# MCU_Module_V2.net
KiCad netlist of a schematic drawn in EAGLE
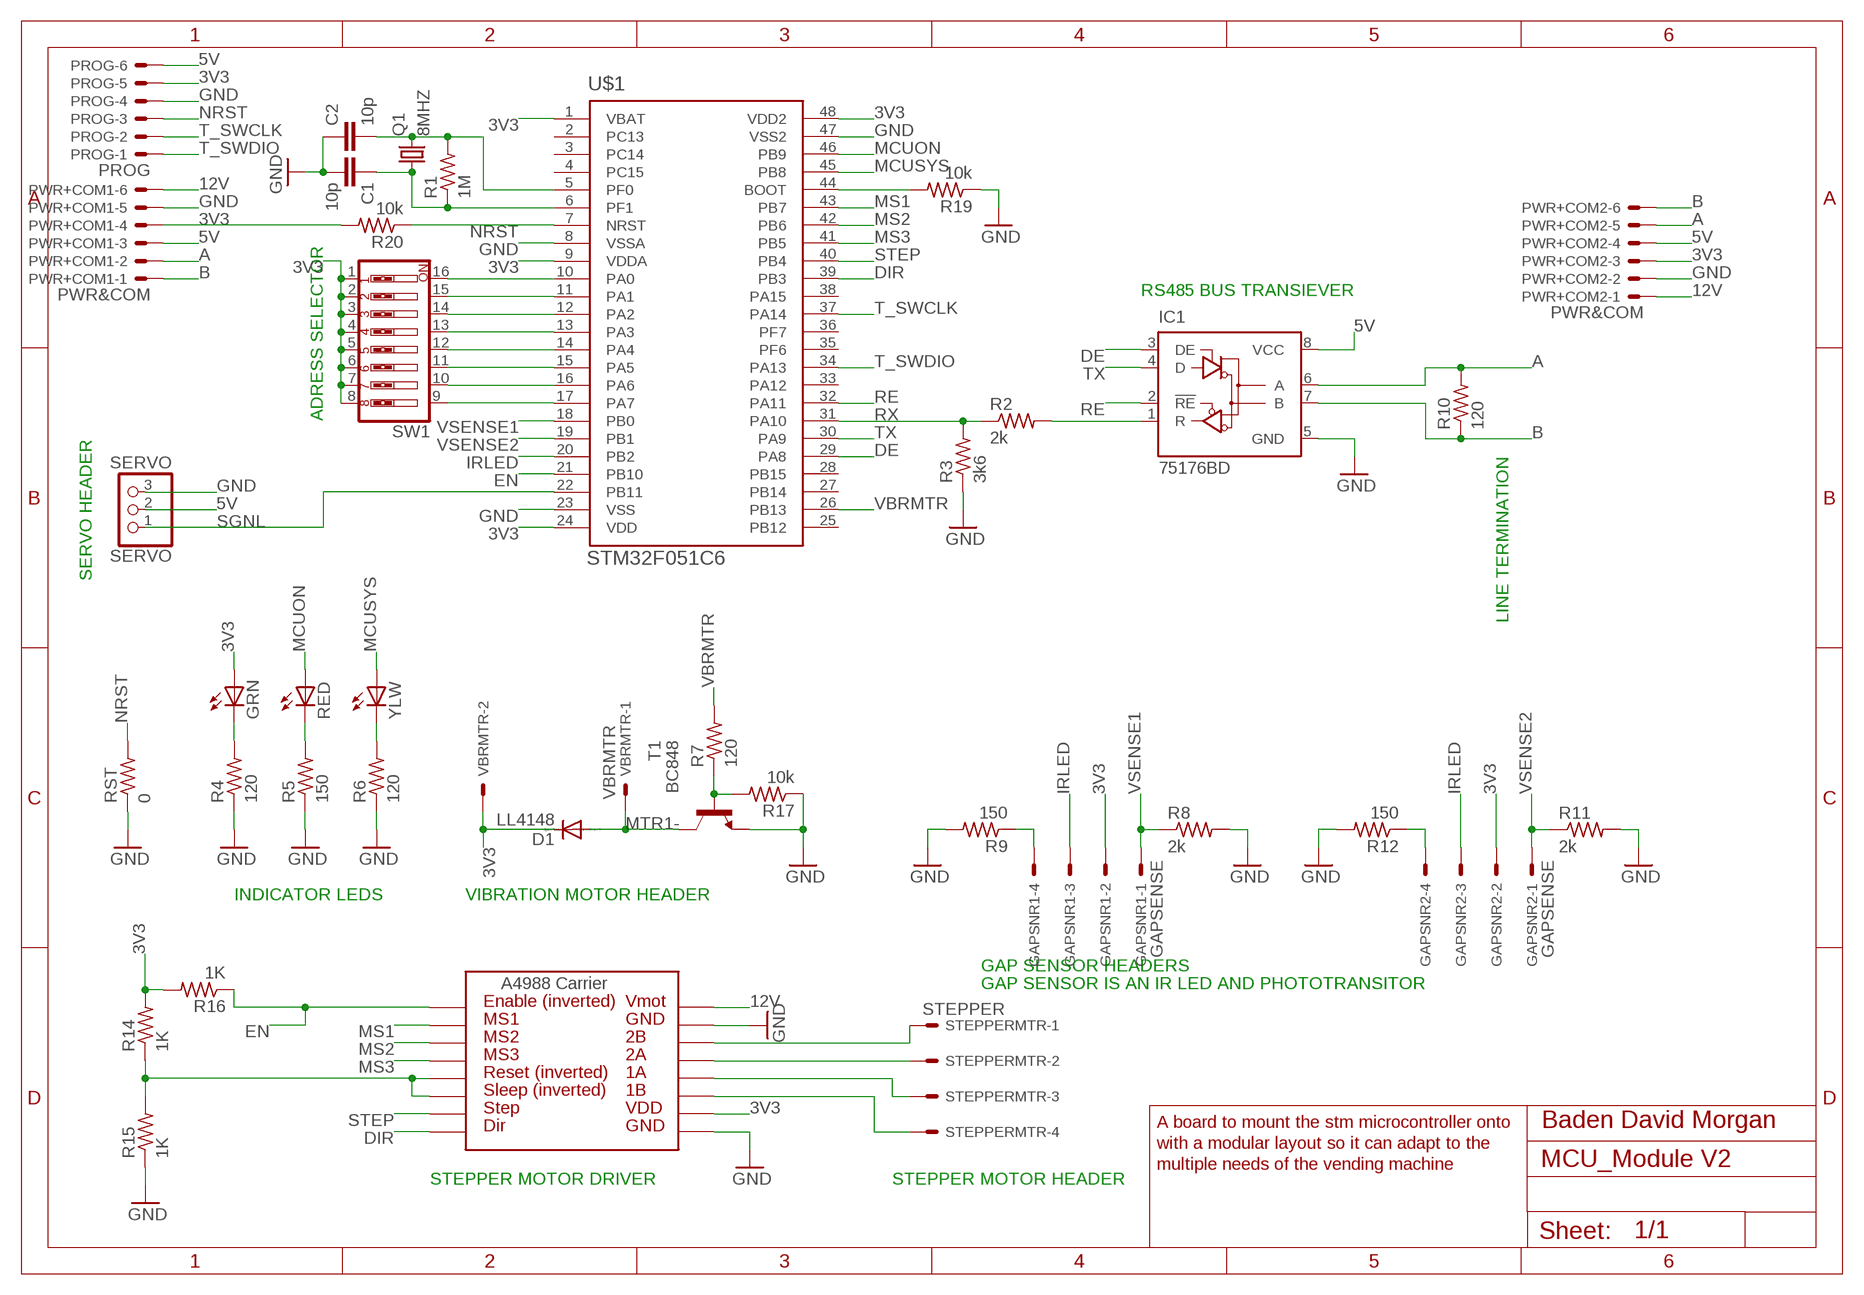
[diagram p0: schematic, sheet 1]

(export (version "E")
  (design (tool "Eeschema 10.0.6"))
  (components
    (comp (ref "C1")
      (value "10p")
      (footprint "eagle-import:C0805")
      (libsource (lib "eagle-import") (part "C-EUC0805"))
    )
    (comp (ref "C2")
      (value "10p")
      (footprint "eagle-import:C0805")
      (libsource (lib "eagle-import") (part "C-EUC0805"))
    )
    (comp (ref "D1")
      (value "LL4148")
      (footprint "eagle-import:SOD80C")
      (libsource (lib "eagle-import") (part "PMLL4150"))
    )
    (comp (ref "GAPSNR1")
      (value "GAPSENSE")
      (footprint "eagle-import:6410-04")
      (libsource (lib "eagle-import") (part "22-?-0427-2041"))
    )
    (comp (ref "GAPSNR2")
      (value "GAPSENSE")
      (footprint "eagle-import:6410-04")
      (libsource (lib "eagle-import") (part "22-?-0427-2041"))
    )
    (comp (ref "GRN")
      (value "LEDSML1206")
      (footprint "eagle-import:SML1206")
      (libsource (lib "eagle-import") (part "LEDSML1206"))
    )
    (comp (ref "IC1")
      (value "75176BD")
      (footprint "eagle-import:D_R-PDSO-G8")
      (libsource (lib "eagle-import") (part "75176AD"))
    )
    (comp (ref "PROG")
      (value "PROG")
      (footprint "eagle-import:6410-06")
      (libsource (lib "eagle-import") (part "22-?-0627-2061"))
    )
    (comp (ref "PWR+COM1")
      (value "PWR&COM")
      (footprint "eagle-import:7395-06")
      (libsource (lib "eagle-import") (part "22-?-0605-7068"))
    )
    (comp (ref "PWR+COM2")
      (value "PWR&COM")
      (footprint "eagle-import:7395-06")
      (libsource (lib "eagle-import") (part "22-?-0605-7068"))
    )
    (comp (ref "Q1")
      (value "8MHZ")
      (footprint "eagle-import:SM49")
      (libsource (lib "eagle-import") (part "CRYSTALSM49"))
    )
    (comp (ref "R1")
      (value "1M")
      (footprint "eagle-import:R0805")
      (libsource (lib "eagle-import") (part "R-US_R0805"))
    )
    (comp (ref "R2")
      (value "2k")
      (footprint "eagle-import:R0805")
      (libsource (lib "eagle-import") (part "resistor_R-US_R0805"))
    )
    (comp (ref "R3")
      (value "3k6")
      (footprint "eagle-import:R0805")
      (libsource (lib "eagle-import") (part "resistor_R-US_R0805"))
    )
    (comp (ref "R4")
      (value "120")
      (footprint "eagle-import:R0805")
      (libsource (lib "eagle-import") (part "R-US_R0805"))
    )
    (comp (ref "R5")
      (value "150")
      (footprint "eagle-import:R0805")
      (libsource (lib "eagle-import") (part "R-US_R0805"))
    )
    (comp (ref "R6")
      (value "120")
      (footprint "eagle-import:R0805")
      (libsource (lib "eagle-import") (part "R-US_R0805"))
    )
    (comp (ref "R7")
      (value "120")
      (footprint "eagle-import:R0805")
      (libsource (lib "eagle-import") (part "R-US_R0805"))
    )
    (comp (ref "R8")
      (value "2k")
      (footprint "eagle-import:R0805")
      (libsource (lib "eagle-import") (part "resistor_R-US_R0805"))
    )
    (comp (ref "R9")
      (value "150")
      (footprint "eagle-import:R0805")
      (libsource (lib "eagle-import") (part "R-US_R0805"))
    )
    (comp (ref "R10")
      (value "120")
      (footprint "eagle-import:R0805")
      (libsource (lib "eagle-import") (part "resistor_R-US_R0805"))
    )
    (comp (ref "R11")
      (value "2k")
      (footprint "eagle-import:R0805")
      (libsource (lib "eagle-import") (part "resistor_R-US_R0805"))
    )
    (comp (ref "R12")
      (value "150")
      (footprint "eagle-import:R0805")
      (libsource (lib "eagle-import") (part "R-US_R0805"))
    )
    (comp (ref "R14")
      (value "1K")
      (footprint "eagle-import:R0805")
      (libsource (lib "eagle-import") (part "R-US_R0805"))
    )
    (comp (ref "R15")
      (value "1K")
      (footprint "eagle-import:R0805")
      (libsource (lib "eagle-import") (part "R-US_R0805"))
    )
    (comp (ref "R16")
      (value "1K")
      (footprint "eagle-import:R0805")
      (libsource (lib "eagle-import") (part "R-US_R0805"))
    )
    (comp (ref "R17")
      (value "10k")
      (footprint "eagle-import:R0805")
      (libsource (lib "eagle-import") (part "R-US_R0805"))
    )
    (comp (ref "R19")
      (value "10k")
      (footprint "eagle-import:R0805")
      (libsource (lib "eagle-import") (part "R-US_R0805"))
    )
    (comp (ref "R20")
      (value "10k")
      (footprint "eagle-import:R0805")
      (libsource (lib "eagle-import") (part "R-US_R0805"))
    )
    (comp (ref "RED")
      (value "LEDSML1206")
      (footprint "eagle-import:SML1206")
      (libsource (lib "eagle-import") (part "LEDSML1206"))
    )
    (comp (ref "RST")
      (value "0")
      (footprint "eagle-import:R0805")
      (libsource (lib "eagle-import") (part "R-US_R0805"))
    )
    (comp (ref "SERVO")
      (value "SERVO")
      (footprint "eagle-import:1X03")
      (libsource (lib "eagle-import") (part "PINHD-1X3"))
    )
    (comp (ref "STEPPERMTR")
      (value "STEPPER")
      (footprint "eagle-import:6410-04")
      (libsource (lib "eagle-import") (part "22-?-0427-2041"))
    )
    (comp (ref "SW1")
      (value "SW_DIP-8")
      (footprint "eagle-import:EDG-08")
      (libsource (lib "eagle-import") (part "SW_DIP-8"))
    )
    (comp (ref "T1")
      (value "BC848")
      (footprint "eagle-import:SOT23")
      (libsource (lib "eagle-import") (part "BC848"))
    )
    (comp (ref "U$1")
      (value "STM32F051C6")
      (footprint "eagle-import:QFP50P900X900X160-48N")
      (libsource (lib "eagle-import") (part "STM32F051C6"))
    )
    (comp (ref "U$2")
      (value "A4983CARRIER")
      (footprint "eagle-import:A4988BREAKOUT")
      (libsource (lib "eagle-import") (part "A4983CARRIER"))
    )
    (comp (ref "VBRMTR")
      (value "VBRMTR")
      (footprint "eagle-import:6410-02")
      (libsource (lib "eagle-import") (part "22-?-0227-2021"))
    )
    (comp (ref "YLW")
      (value "LEDSML1206")
      (footprint "eagle-import:SML1206")
      (libsource (lib "eagle-import") (part "LEDSML1206"))
    )
  )
  (nets
    (net (code "1") (name "/3V3") (class "Default")
      (node (ref "D1") (pin "C") (pinfunction "C_C") (pintype "passive"))
      (node (ref "GAPSNR1") (pin "2") (pinfunction "S_2") (pintype "passive"))
      (node (ref "GAPSNR2") (pin "2") (pinfunction "S_2") (pintype "passive"))
      (node (ref "GRN") (pin "A") (pinfunction "A_A") (pintype "passive"))
      (node (ref "PROG") (pin "5") (pinfunction "S_5") (pintype "passive"))
      (node (ref "PWR+COM1") (pin "4") (pinfunction "S_4") (pintype "passive"))
      (node (ref "PWR+COM2") (pin "3") (pinfunction "S_3") (pintype "passive"))
      (node (ref "R14") (pin "2") (pinfunction "2_2") (pintype "passive"))
      (node (ref "R16") (pin "2") (pinfunction "2_2") (pintype "passive"))
      (node (ref "R20") (pin "2") (pinfunction "2_2") (pintype "passive"))
      (node (ref "SW1") (pin "1") (pinfunction "1_1") (pintype "passive"))
      (node (ref "SW1") (pin "2") (pinfunction "2_2") (pintype "passive"))
      (node (ref "SW1") (pin "3") (pinfunction "3_3") (pintype "passive"))
      (node (ref "SW1") (pin "4") (pinfunction "4_4") (pintype "passive"))
      (node (ref "SW1") (pin "5") (pinfunction "5_5") (pintype "passive"))
      (node (ref "SW1") (pin "6") (pinfunction "6_6") (pintype "passive"))
      (node (ref "SW1") (pin "7") (pinfunction "7_7") (pintype "passive"))
      (node (ref "SW1") (pin "8") (pinfunction "8_8") (pintype "passive"))
      (node (ref "U$1") (pin "1") (pinfunction "VBAT_1") (pintype "bidirectional"))
      (node (ref "U$1") (pin "24") (pinfunction "VDD_24") (pintype "bidirectional"))
      (node (ref "U$1") (pin "48") (pinfunction "VDD2_48") (pintype "bidirectional"))
      (node (ref "U$1") (pin "9") (pinfunction "VDDA_9") (pintype "bidirectional"))
      (node (ref "U$2") (pin "VDD") (pinfunction "VDD_VDD") (pintype "power_in"))
      (node (ref "VBRMTR") (pin "2") (pinfunction "S_2") (pintype "passive"))
    )
    (net (code "2") (name "/5V") (class "Default")
      (node (ref "IC1") (pin "8") (pinfunction "VCC_8") (pintype "power_in"))
      (node (ref "PROG") (pin "6") (pinfunction "S_6") (pintype "passive"))
      (node (ref "PWR+COM1") (pin "3") (pinfunction "S_3") (pintype "passive"))
      (node (ref "PWR+COM2") (pin "4") (pinfunction "S_4") (pintype "passive"))
      (node (ref "SERVO") (pin "2") (pinfunction "2_2") (pintype "passive"))
    )
    (net (code "3") (name "/12V") (class "Default")
      (node (ref "PWR+COM1") (pin "6") (pinfunction "S_6") (pintype "passive"))
      (node (ref "PWR+COM2") (pin "1") (pinfunction "S_1") (pintype "passive"))
      (node (ref "U$2") (pin "VMOT") (pinfunction "VMOT_VMOT") (pintype "power_in"))
    )
    (net (code "4") (name "/A") (class "Default")
      (node (ref "IC1") (pin "6") (pinfunction "A_6") (pintype "output"))
      (node (ref "PWR+COM1") (pin "2") (pinfunction "S_2") (pintype "passive"))
      (node (ref "PWR+COM2") (pin "5") (pinfunction "S_5") (pintype "passive"))
      (node (ref "R10") (pin "2") (pinfunction "2_2") (pintype "passive"))
    )
    (net (code "5") (name "/B") (class "Default")
      (node (ref "IC1") (pin "7") (pinfunction "B_7") (pintype "output"))
      (node (ref "PWR+COM1") (pin "1") (pinfunction "S_1") (pintype "passive"))
      (node (ref "PWR+COM2") (pin "6") (pinfunction "S_6") (pintype "passive"))
      (node (ref "R10") (pin "1") (pinfunction "1_1") (pintype "passive"))
    )
    (net (code "6") (name "/DE") (class "Default")
      (node (ref "IC1") (pin "3") (pinfunction "DE_3") (pintype "input"))
      (node (ref "U$1") (pin "29") (pinfunction "PA8_29") (pintype "bidirectional"))
    )
    (net (code "7") (name "/DIR") (class "Default")
      (node (ref "U$1") (pin "39") (pinfunction "PB3_39") (pintype "bidirectional"))
      (node (ref "U$2") (pin "DIR") (pinfunction "DIR_DIR") (pintype "input"))
    )
    (net (code "8") (name "/EN") (class "Default")
      (node (ref "R16") (pin "1") (pinfunction "1_1") (pintype "passive"))
      (node (ref "U$1") (pin "21") (pinfunction "PB10_21") (pintype "bidirectional"))
      (node (ref "U$2") (pin "EN") (pinfunction "EN_EN") (pintype "input"))
    )
    (net (code "9") (name "/IRLED") (class "Default")
      (node (ref "GAPSNR1") (pin "3") (pinfunction "S_3") (pintype "passive"))
      (node (ref "GAPSNR2") (pin "3") (pinfunction "S_3") (pintype "passive"))
      (node (ref "U$1") (pin "20") (pinfunction "PB2_20") (pintype "bidirectional"))
    )
    (net (code "10") (name "/MCUON") (class "Default")
      (node (ref "RED") (pin "A") (pinfunction "A_A") (pintype "passive"))
      (node (ref "U$1") (pin "46") (pinfunction "PB9_46") (pintype "bidirectional"))
    )
    (net (code "11") (name "/MCUSYS") (class "Default")
      (node (ref "U$1") (pin "45") (pinfunction "PB8_45") (pintype "bidirectional"))
      (node (ref "YLW") (pin "A") (pinfunction "A_A") (pintype "passive"))
    )
    (net (code "12") (name "/MS1") (class "Default")
      (node (ref "U$1") (pin "43") (pinfunction "PB7_43") (pintype "bidirectional"))
      (node (ref "U$2") (pin "MS1") (pinfunction "MS1_MS1") (pintype "input"))
    )
    (net (code "13") (name "/MS2") (class "Default")
      (node (ref "U$1") (pin "42") (pinfunction "PB6_42") (pintype "bidirectional"))
      (node (ref "U$2") (pin "MS2") (pinfunction "MS2_MS2") (pintype "input"))
    )
    (net (code "14") (name "/MS3") (class "Default")
      (node (ref "U$1") (pin "41") (pinfunction "PB5_41") (pintype "bidirectional"))
      (node (ref "U$2") (pin "MS3") (pinfunction "MS3_MS3") (pintype "input"))
    )
    (net (code "15") (name "/MTR1-") (class "Default")
      (node (ref "D1") (pin "A") (pinfunction "A_A") (pintype "passive"))
      (node (ref "T1") (pin "3") (pinfunction "C_3") (pintype "passive"))
      (node (ref "VBRMTR") (pin "1") (pinfunction "S_1") (pintype "passive"))
    )
    (net (code "16") (name "/NRST") (class "Default")
      (node (ref "PROG") (pin "3") (pinfunction "S_3") (pintype "passive"))
      (node (ref "R20") (pin "1") (pinfunction "1_1") (pintype "passive"))
      (node (ref "RST") (pin "2") (pinfunction "2_2") (pintype "passive"))
      (node (ref "U$1") (pin "7") (pinfunction "NRST_7") (pintype "bidirectional"))
    )
    (net (code "17") (name "/RE") (class "Default")
      (node (ref "IC1") (pin "2") (pinfunction "~{RE}_2") (pintype "input"))
      (node (ref "U$1") (pin "32") (pinfunction "PA11_32") (pintype "bidirectional"))
    )
    (net (code "18") (name "/RX") (class "Default")
      (node (ref "R2") (pin "1") (pinfunction "1_1") (pintype "passive"))
      (node (ref "R3") (pin "2") (pinfunction "2_2") (pintype "passive"))
      (node (ref "U$1") (pin "31") (pinfunction "PA10_31") (pintype "bidirectional"))
    )
    (net (code "19") (name "/SGNL") (class "Default")
      (node (ref "SERVO") (pin "1") (pinfunction "1_1") (pintype "passive"))
      (node (ref "U$1") (pin "22") (pinfunction "PB11_22") (pintype "bidirectional"))
    )
    (net (code "20") (name "/STEP") (class "Default")
      (node (ref "U$1") (pin "40") (pinfunction "PB4_40") (pintype "bidirectional"))
      (node (ref "U$2") (pin "STEP") (pinfunction "STEP_STEP") (pintype "input"))
    )
    (net (code "21") (name "/TX") (class "Default")
      (node (ref "IC1") (pin "4") (pinfunction "D_4") (pintype "input"))
      (node (ref "U$1") (pin "30") (pinfunction "PA9_30") (pintype "bidirectional"))
    )
    (net (code "22") (name "/T_SWCLK") (class "Default")
      (node (ref "PROG") (pin "2") (pinfunction "S_2") (pintype "passive"))
      (node (ref "U$1") (pin "37") (pinfunction "PA14_37") (pintype "bidirectional"))
    )
    (net (code "23") (name "/T_SWDIO") (class "Default")
      (node (ref "PROG") (pin "1") (pinfunction "S_1") (pintype "passive"))
      (node (ref "U$1") (pin "34") (pinfunction "PA13_34") (pintype "bidirectional"))
    )
    (net (code "24") (name "/VBRMTR") (class "Default")
      (node (ref "R7") (pin "2") (pinfunction "2_2") (pintype "passive"))
      (node (ref "U$1") (pin "26") (pinfunction "PB13_26") (pintype "bidirectional"))
    )
    (net (code "25") (name "/VSENSE1") (class "Default")
      (node (ref "GAPSNR1") (pin "1") (pinfunction "S_1") (pintype "passive"))
      (node (ref "R8") (pin "1") (pinfunction "1_1") (pintype "passive"))
      (node (ref "U$1") (pin "18") (pinfunction "PB0_18") (pintype "bidirectional"))
    )
    (net (code "26") (name "/VSENSE2") (class "Default")
      (node (ref "GAPSNR2") (pin "1") (pinfunction "S_1") (pintype "passive"))
      (node (ref "R11") (pin "1") (pinfunction "1_1") (pintype "passive"))
      (node (ref "U$1") (pin "19") (pinfunction "PB1_19") (pintype "bidirectional"))
    )
    (net (code "27") (name "GND") (class "Default")
      (node (ref "C1") (pin "2") (pinfunction "2_2") (pintype "passive"))
      (node (ref "C2") (pin "1") (pinfunction "1_1") (pintype "passive"))
      (node (ref "IC1") (pin "5") (pinfunction "GND_5") (pintype "power_in"))
      (node (ref "PROG") (pin "4") (pinfunction "S_4") (pintype "passive"))
      (node (ref "PWR+COM1") (pin "5") (pinfunction "S_5") (pintype "passive"))
      (node (ref "PWR+COM2") (pin "2") (pinfunction "S_2") (pintype "passive"))
      (node (ref "R11") (pin "2") (pinfunction "2_2") (pintype "passive"))
      (node (ref "R12") (pin "2") (pinfunction "2_2") (pintype "passive"))
      (node (ref "R15") (pin "1") (pinfunction "1_1") (pintype "passive"))
      (node (ref "R17") (pin "1") (pinfunction "1_1") (pintype "passive"))
      (node (ref "R19") (pin "1") (pinfunction "1_1") (pintype "passive"))
      (node (ref "R3") (pin "1") (pinfunction "1_1") (pintype "passive"))
      (node (ref "R4") (pin "1") (pinfunction "1_1") (pintype "passive"))
      (node (ref "R5") (pin "1") (pinfunction "1_1") (pintype "passive"))
      (node (ref "R6") (pin "1") (pinfunction "1_1") (pintype "passive"))
      (node (ref "R8") (pin "2") (pinfunction "2_2") (pintype "passive"))
      (node (ref "R9") (pin "2") (pinfunction "2_2") (pintype "passive"))
      (node (ref "RST") (pin "1") (pinfunction "1_1") (pintype "passive"))
      (node (ref "SERVO") (pin "3") (pinfunction "3_3") (pintype "passive"))
      (node (ref "T1") (pin "2") (pinfunction "E_2") (pintype "passive"))
      (node (ref "U$1") (pin "23") (pinfunction "VSS_23") (pintype "bidirectional"))
      (node (ref "U$1") (pin "47") (pinfunction "VSS2_47") (pintype "bidirectional"))
      (node (ref "U$1") (pin "8") (pinfunction "VSSA_8") (pintype "bidirectional"))
      (node (ref "U$2") (pin "GND") (pinfunction "GND_GND") (pintype "power_in"))
      (node (ref "U$2") (pin "GND@0") (pinfunction "GND_GND@0") (pintype "power_in"))
    )
    (net (code "28") (name "Net-(GAPSNR1D-S)") (class "Default")
      (node (ref "GAPSNR1") (pin "4") (pinfunction "S_4") (pintype "passive"))
      (node (ref "R9") (pin "1") (pinfunction "1_1") (pintype "passive"))
    )
    (net (code "29") (name "Net-(GAPSNR2D-S)") (class "Default")
      (node (ref "GAPSNR2") (pin "4") (pinfunction "S_4") (pintype "passive"))
      (node (ref "R12") (pin "1") (pinfunction "1_1") (pintype "passive"))
    )
    (net (code "30") (name "Net-(GRN-PadC)") (class "Default")
      (node (ref "GRN") (pin "C") (pinfunction "C_C") (pintype "passive"))
      (node (ref "R4") (pin "2") (pinfunction "2_2") (pintype "passive"))
    )
    (net (code "31") (name "Net-(IC1-R)") (class "Default")
      (node (ref "IC1") (pin "1") (pinfunction "R_1") (pintype "input"))
      (node (ref "R2") (pin "2") (pinfunction "2_2") (pintype "passive"))
    )
    (net (code "32") (name "Net-(R5-Pad2)") (class "Default")
      (node (ref "R5") (pin "2") (pinfunction "2_2") (pintype "passive"))
      (node (ref "RED") (pin "C") (pinfunction "C_C") (pintype "passive"))
    )
    (net (code "33") (name "Net-(R6-Pad2)") (class "Default")
      (node (ref "R6") (pin "2") (pinfunction "2_2") (pintype "passive"))
      (node (ref "YLW") (pin "C") (pinfunction "C_C") (pintype "passive"))
    )
    (net (code "34") (name "Net-(STEPPERMTRA-S)") (class "Default")
      (node (ref "STEPPERMTR") (pin "1") (pinfunction "S_1") (pintype "passive"))
      (node (ref "U$2") (pin "2B") (pinfunction "2B_2B") (pintype "output"))
    )
    (net (code "35") (name "Net-(STEPPERMTRB-S)") (class "Default")
      (node (ref "STEPPERMTR") (pin "2") (pinfunction "S_2") (pintype "passive"))
      (node (ref "U$2") (pin "2A") (pinfunction "2A_2A") (pintype "output"))
    )
    (net (code "36") (name "Net-(STEPPERMTRC-S)") (class "Default")
      (node (ref "STEPPERMTR") (pin "3") (pinfunction "S_3") (pintype "passive"))
      (node (ref "U$2") (pin "1A") (pinfunction "1A_1A") (pintype "output"))
    )
    (net (code "37") (name "Net-(STEPPERMTRD-S)") (class "Default")
      (node (ref "STEPPERMTR") (pin "4") (pinfunction "S_4") (pintype "passive"))
      (node (ref "U$2") (pin "1B") (pinfunction "1B_1B") (pintype "output"))
    )
    (net (code "38") (name "Net-(T1-B)") (class "Default")
      (node (ref "R17") (pin "2") (pinfunction "2_2") (pintype "passive"))
      (node (ref "R7") (pin "1") (pinfunction "1_1") (pintype "passive"))
      (node (ref "T1") (pin "1") (pinfunction "B_1") (pintype "passive"))
    )
    (net (code "39") (name "Net-(U$1-BOOT)") (class "Default")
      (node (ref "R19") (pin "2") (pinfunction "2_2") (pintype "passive"))
      (node (ref "U$1") (pin "44") (pinfunction "BOOT_44") (pintype "bidirectional"))
    )
    (net (code "40") (name "Net-(U$1-PA0)") (class "Default")
      (node (ref "SW1") (pin "16") (pinfunction "16_16") (pintype "passive"))
      (node (ref "U$1") (pin "10") (pinfunction "PA0_10") (pintype "bidirectional"))
    )
    (net (code "41") (name "Net-(U$1-PA1)") (class "Default")
      (node (ref "SW1") (pin "15") (pinfunction "15_15") (pintype "passive"))
      (node (ref "U$1") (pin "11") (pinfunction "PA1_11") (pintype "bidirectional"))
    )
    (net (code "42") (name "Net-(U$1-PA2)") (class "Default")
      (node (ref "SW1") (pin "14") (pinfunction "14_14") (pintype "passive"))
      (node (ref "U$1") (pin "12") (pinfunction "PA2_12") (pintype "bidirectional"))
    )
    (net (code "43") (name "Net-(U$1-PA3)") (class "Default")
      (node (ref "SW1") (pin "13") (pinfunction "13_13") (pintype "passive"))
      (node (ref "U$1") (pin "13") (pinfunction "PA3_13") (pintype "bidirectional"))
    )
    (net (code "44") (name "Net-(U$1-PA4)") (class "Default")
      (node (ref "SW1") (pin "12") (pinfunction "12_12") (pintype "passive"))
      (node (ref "U$1") (pin "14") (pinfunction "PA4_14") (pintype "bidirectional"))
    )
    (net (code "45") (name "Net-(U$1-PA5)") (class "Default")
      (node (ref "SW1") (pin "11") (pinfunction "11_11") (pintype "passive"))
      (node (ref "U$1") (pin "15") (pinfunction "PA5_15") (pintype "bidirectional"))
    )
    (net (code "46") (name "Net-(U$1-PA6)") (class "Default")
      (node (ref "SW1") (pin "10") (pinfunction "10_10") (pintype "passive"))
      (node (ref "U$1") (pin "16") (pinfunction "PA6_16") (pintype "bidirectional"))
    )
    (net (code "47") (name "Net-(U$1-PA7)") (class "Default")
      (node (ref "SW1") (pin "9") (pinfunction "9_9") (pintype "passive"))
      (node (ref "U$1") (pin "17") (pinfunction "PA7_17") (pintype "bidirectional"))
    )
    (net (code "48") (name "Net-(U$1-PF0)") (class "Default")
      (node (ref "C2") (pin "2") (pinfunction "2_2") (pintype "passive"))
      (node (ref "Q1") (pin "2") (pinfunction "2_2") (pintype "passive"))
      (node (ref "R1") (pin "2") (pinfunction "2_2") (pintype "passive"))
      (node (ref "U$1") (pin "5") (pinfunction "PF0_5") (pintype "bidirectional"))
    )
    (net (code "49") (name "Net-(U$1-PF1)") (class "Default")
      (node (ref "C1") (pin "1") (pinfunction "1_1") (pintype "passive"))
      (node (ref "Q1") (pin "1") (pinfunction "1_1") (pintype "passive"))
      (node (ref "R1") (pin "1") (pinfunction "1_1") (pintype "passive"))
      (node (ref "U$1") (pin "6") (pinfunction "PF1_6") (pintype "bidirectional"))
    )
    (net (code "50") (name "Net-(U$2-SLEEP)") (class "Default")
      (node (ref "R14") (pin "1") (pinfunction "1_1") (pintype "passive"))
      (node (ref "R15") (pin "2") (pinfunction "2_2") (pintype "passive"))
      (node (ref "U$2") (pin "RST") (pinfunction "RST_RST") (pintype "input"))
      (node (ref "U$2") (pin "SLP") (pinfunction "SLEEP_SLP") (pintype "input"))
    )
    (net (code "51") (name "unconnected-(U$1-PA12-Pad33)") (class "Default")
      (node (ref "U$1") (pin "33") (pinfunction "PA12_33") (pintype "bidirectional"))
    )
    (net (code "52") (name "unconnected-(U$1-PA15-Pad38)") (class "Default")
      (node (ref "U$1") (pin "38") (pinfunction "PA15_38") (pintype "bidirectional"))
    )
    (net (code "53") (name "unconnected-(U$1-PB12-Pad25)") (class "Default")
      (node (ref "U$1") (pin "25") (pinfunction "PB12_25") (pintype "bidirectional"))
    )
    (net (code "54") (name "unconnected-(U$1-PB14-Pad27)") (class "Default")
      (node (ref "U$1") (pin "27") (pinfunction "PB14_27") (pintype "bidirectional"))
    )
    (net (code "55") (name "unconnected-(U$1-PB15-Pad28)") (class "Default")
      (node (ref "U$1") (pin "28") (pinfunction "PB15_28") (pintype "bidirectional"))
    )
    (net (code "56") (name "unconnected-(U$1-PC13-Pad2)") (class "Default")
      (node (ref "U$1") (pin "2") (pinfunction "PC13_2") (pintype "bidirectional"))
    )
    (net (code "57") (name "unconnected-(U$1-PC14-Pad3)") (class "Default")
      (node (ref "U$1") (pin "3") (pinfunction "PC14_3") (pintype "bidirectional"))
    )
    (net (code "58") (name "unconnected-(U$1-PC15-Pad4)") (class "Default")
      (node (ref "U$1") (pin "4") (pinfunction "PC15_4") (pintype "bidirectional"))
    )
    (net (code "59") (name "unconnected-(U$1-PF6-Pad35)") (class "Default")
      (node (ref "U$1") (pin "35") (pinfunction "PF6_35") (pintype "bidirectional"))
    )
    (net (code "60") (name "unconnected-(U$1-PF7-Pad36)") (class "Default")
      (node (ref "U$1") (pin "36") (pinfunction "PF7_36") (pintype "bidirectional"))
    )
  )
)
